# iot-terminal-shield.net
KiCad netlist of a schematic drawn in EAGLE
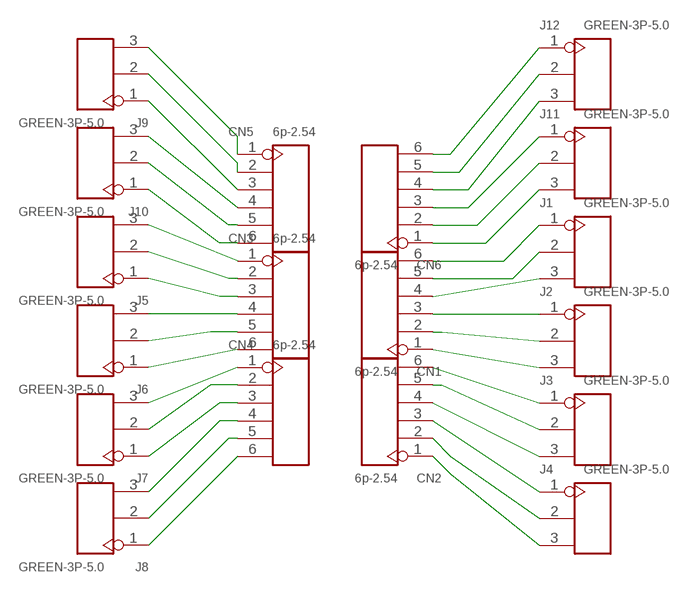
[diagram p0: schematic, sheet 1]

(export (version "E")
  (design (tool "Eeschema 10.0.6"))
  (components
    (comp (ref "CN1")
      (value "6p-2.54")
      (footprint "eagle-import:H6-2.54")
      (fields (field (name "MPN") "F185-1106A1BSYC1"))
      (libsource (lib "eagle-import") (part "DIP-BLACK-FEMALE-HEADER-VERT(6P-2.54)"))
    )
    (comp (ref "CN2")
      (value "6p-2.54")
      (footprint "eagle-import:H6-2.54")
      (fields (field (name "MPN") "F185-1106A1BSYC1"))
      (libsource (lib "eagle-import") (part "DIP-BLACK-FEMALE-HEADER-VERT(6P-2.54)"))
    )
    (comp (ref "CN3")
      (value "6p-2.54")
      (footprint "eagle-import:H6-2.54")
      (fields (field (name "MPN") "F185-1106A1BSYC1"))
      (libsource (lib "eagle-import") (part "DIP-BLACK-FEMALE-HEADER-VERT(6P-2.54)"))
    )
    (comp (ref "CN4")
      (value "6p-2.54")
      (footprint "eagle-import:H6-2.54")
      (fields (field (name "MPN") "F185-1106A1BSYC1"))
      (libsource (lib "eagle-import") (part "DIP-BLACK-FEMALE-HEADER-VERT(6P-2.54)"))
    )
    (comp (ref "CN5")
      (value "6p-2.54")
      (footprint "eagle-import:H6-2.54")
      (fields (field (name "MPN") "F185-1106A1BSYC1"))
      (libsource (lib "eagle-import") (part "DIP-BLACK-FEMALE-HEADER-VERT(6P-2.54)"))
    )
    (comp (ref "CN6")
      (value "6p-2.54")
      (footprint "eagle-import:H6-2.54")
      (fields (field (name "MPN") "F185-1106A1BSYC1"))
      (libsource (lib "eagle-import") (part "DIP-BLACK-FEMALE-HEADER-VERT(6P-2.54)"))
    )
    (comp (ref "J1")
      (value "GREEN-3P-5.0")
      (footprint "eagle-import:H3-5.0-15.5X8.0MM")
      (libsource (lib "eagle-import") (part "SCREW-TERMINAL-GREEN(3P-5.0)"))
    )
    (comp (ref "J2")
      (value "GREEN-3P-5.0")
      (footprint "eagle-import:H3-5.0-15.5X8.0MM")
      (libsource (lib "eagle-import") (part "SCREW-TERMINAL-GREEN(3P-5.0)"))
    )
    (comp (ref "J3")
      (value "GREEN-3P-5.0")
      (footprint "eagle-import:H3-5.0-15.5X8.0MM")
      (libsource (lib "eagle-import") (part "SCREW-TERMINAL-GREEN(3P-5.0)"))
    )
    (comp (ref "J4")
      (value "GREEN-3P-5.0")
      (footprint "eagle-import:H3-5.0-15.5X8.0MM")
      (libsource (lib "eagle-import") (part "SCREW-TERMINAL-GREEN(3P-5.0)"))
    )
    (comp (ref "J5")
      (value "GREEN-3P-5.0")
      (footprint "eagle-import:H3-5.0-15.5X8.0MM")
      (libsource (lib "eagle-import") (part "SCREW-TERMINAL-GREEN(3P-5.0)"))
    )
    (comp (ref "J6")
      (value "GREEN-3P-5.0")
      (footprint "eagle-import:H3-5.0-15.5X8.0MM")
      (libsource (lib "eagle-import") (part "SCREW-TERMINAL-GREEN(3P-5.0)"))
    )
    (comp (ref "J7")
      (value "GREEN-3P-5.0")
      (footprint "eagle-import:H3-5.0-15.5X8.0MM")
      (libsource (lib "eagle-import") (part "SCREW-TERMINAL-GREEN(3P-5.0)"))
    )
    (comp (ref "J8")
      (value "GREEN-3P-5.0")
      (footprint "eagle-import:H3-5.0-15.5X8.0MM")
      (libsource (lib "eagle-import") (part "SCREW-TERMINAL-GREEN(3P-5.0)"))
    )
    (comp (ref "J9")
      (value "GREEN-3P-5.0")
      (footprint "eagle-import:H3-5.0-15.5X8.0MM")
      (libsource (lib "eagle-import") (part "SCREW-TERMINAL-GREEN(3P-5.0)"))
    )
    (comp (ref "J10")
      (value "GREEN-3P-5.0")
      (footprint "eagle-import:H3-5.0-15.5X8.0MM")
      (libsource (lib "eagle-import") (part "SCREW-TERMINAL-GREEN(3P-5.0)"))
    )
    (comp (ref "J11")
      (value "GREEN-3P-5.0")
      (footprint "eagle-import:H3-5.0-15.5X8.0MM")
      (libsource (lib "eagle-import") (part "SCREW-TERMINAL-GREEN(3P-5.0)"))
    )
    (comp (ref "J12")
      (value "GREEN-3P-5.0")
      (footprint "eagle-import:H3-5.0-15.5X8.0MM")
      (libsource (lib "eagle-import") (part "SCREW-TERMINAL-GREEN(3P-5.0)"))
    )
  )
  (nets
    (net (code "1") (name "Net-(J1-P$1)") (class "Default")
      (node (ref "CN1") (pin "6") (pinfunction "6_6") (pintype "bidirectional"))
      (node (ref "J1") (pin "1") (pinfunction "P$1_1") (pintype "bidirectional"))
    )
    (net (code "2") (name "Net-(J1-P$2)") (class "Default")
      (node (ref "CN1") (pin "5") (pinfunction "5_5") (pintype "bidirectional"))
      (node (ref "J1") (pin "2") (pinfunction "P$2_2") (pintype "bidirectional"))
    )
    (net (code "3") (name "Net-(J1-P$3)") (class "Default")
      (node (ref "CN1") (pin "4") (pinfunction "4_4") (pintype "bidirectional"))
      (node (ref "J1") (pin "3") (pinfunction "P$3_3") (pintype "bidirectional"))
    )
    (net (code "4") (name "Net-(J2-P$1)") (class "Default")
      (node (ref "CN1") (pin "3") (pinfunction "3_3") (pintype "bidirectional"))
      (node (ref "J2") (pin "1") (pinfunction "P$1_1") (pintype "bidirectional"))
    )
    (net (code "5") (name "Net-(J2-P$2)") (class "Default")
      (node (ref "CN1") (pin "2") (pinfunction "2_2") (pintype "bidirectional"))
      (node (ref "J2") (pin "2") (pinfunction "P$2_2") (pintype "bidirectional"))
    )
    (net (code "6") (name "Net-(J2-P$3)") (class "Default")
      (node (ref "CN1") (pin "1") (pinfunction "1_1") (pintype "bidirectional"))
      (node (ref "J2") (pin "3") (pinfunction "P$3_3") (pintype "bidirectional"))
    )
    (net (code "7") (name "Net-(J3-P$1)") (class "Default")
      (node (ref "CN2") (pin "6") (pinfunction "6_6") (pintype "bidirectional"))
      (node (ref "J3") (pin "1") (pinfunction "P$1_1") (pintype "bidirectional"))
    )
    (net (code "8") (name "Net-(J3-P$2)") (class "Default")
      (node (ref "CN2") (pin "5") (pinfunction "5_5") (pintype "bidirectional"))
      (node (ref "J3") (pin "2") (pinfunction "P$2_2") (pintype "bidirectional"))
    )
    (net (code "9") (name "Net-(J3-P$3)") (class "Default")
      (node (ref "CN2") (pin "4") (pinfunction "4_4") (pintype "bidirectional"))
      (node (ref "J3") (pin "3") (pinfunction "P$3_3") (pintype "bidirectional"))
    )
    (net (code "10") (name "Net-(J4-P$1)") (class "Default")
      (node (ref "CN2") (pin "3") (pinfunction "3_3") (pintype "bidirectional"))
      (node (ref "J4") (pin "1") (pinfunction "P$1_1") (pintype "bidirectional"))
    )
    (net (code "11") (name "Net-(J4-P$2)") (class "Default")
      (node (ref "CN2") (pin "2") (pinfunction "2_2") (pintype "bidirectional"))
      (node (ref "J4") (pin "2") (pinfunction "P$2_2") (pintype "bidirectional"))
    )
    (net (code "12") (name "Net-(J4-P$3)") (class "Default")
      (node (ref "CN2") (pin "1") (pinfunction "1_1") (pintype "bidirectional"))
      (node (ref "J4") (pin "3") (pinfunction "P$3_3") (pintype "bidirectional"))
    )
    (net (code "13") (name "Net-(J5-P$1)") (class "Default")
      (node (ref "CN3") (pin "3") (pinfunction "3_3") (pintype "bidirectional"))
      (node (ref "J5") (pin "1") (pinfunction "P$1_1") (pintype "bidirectional"))
    )
    (net (code "14") (name "Net-(J5-P$2)") (class "Default")
      (node (ref "CN3") (pin "2") (pinfunction "2_2") (pintype "bidirectional"))
      (node (ref "J5") (pin "2") (pinfunction "P$2_2") (pintype "bidirectional"))
    )
    (net (code "15") (name "Net-(J5-P$3)") (class "Default")
      (node (ref "CN3") (pin "1") (pinfunction "1_1") (pintype "bidirectional"))
      (node (ref "J5") (pin "3") (pinfunction "P$3_3") (pintype "bidirectional"))
    )
    (net (code "16") (name "Net-(J6-P$1)") (class "Default")
      (node (ref "CN3") (pin "6") (pinfunction "6_6") (pintype "bidirectional"))
      (node (ref "J6") (pin "1") (pinfunction "P$1_1") (pintype "bidirectional"))
    )
    (net (code "17") (name "Net-(J6-P$2)") (class "Default")
      (node (ref "CN3") (pin "5") (pinfunction "5_5") (pintype "bidirectional"))
      (node (ref "J6") (pin "2") (pinfunction "P$2_2") (pintype "bidirectional"))
    )
    (net (code "18") (name "Net-(J6-P$3)") (class "Default")
      (node (ref "CN3") (pin "4") (pinfunction "4_4") (pintype "bidirectional"))
      (node (ref "J6") (pin "3") (pinfunction "P$3_3") (pintype "bidirectional"))
    )
    (net (code "19") (name "Net-(J7-P$1)") (class "Default")
      (node (ref "CN4") (pin "3") (pinfunction "3_3") (pintype "bidirectional"))
      (node (ref "J7") (pin "1") (pinfunction "P$1_1") (pintype "bidirectional"))
    )
    (net (code "20") (name "Net-(J7-P$2)") (class "Default")
      (node (ref "CN4") (pin "2") (pinfunction "2_2") (pintype "bidirectional"))
      (node (ref "J7") (pin "2") (pinfunction "P$2_2") (pintype "bidirectional"))
    )
    (net (code "21") (name "Net-(J7-P$3)") (class "Default")
      (node (ref "CN4") (pin "1") (pinfunction "1_1") (pintype "bidirectional"))
      (node (ref "J7") (pin "3") (pinfunction "P$3_3") (pintype "bidirectional"))
    )
    (net (code "22") (name "Net-(J8-P$1)") (class "Default")
      (node (ref "CN4") (pin "6") (pinfunction "6_6") (pintype "bidirectional"))
      (node (ref "J8") (pin "1") (pinfunction "P$1_1") (pintype "bidirectional"))
    )
    (net (code "23") (name "Net-(J8-P$2)") (class "Default")
      (node (ref "CN4") (pin "5") (pinfunction "5_5") (pintype "bidirectional"))
      (node (ref "J8") (pin "2") (pinfunction "P$2_2") (pintype "bidirectional"))
    )
    (net (code "24") (name "Net-(J8-P$3)") (class "Default")
      (node (ref "CN4") (pin "4") (pinfunction "4_4") (pintype "bidirectional"))
      (node (ref "J8") (pin "3") (pinfunction "P$3_3") (pintype "bidirectional"))
    )
    (net (code "25") (name "Net-(J9-P$1)") (class "Default")
      (node (ref "CN5") (pin "3") (pinfunction "3_3") (pintype "bidirectional"))
      (node (ref "J9") (pin "1") (pinfunction "P$1_1") (pintype "bidirectional"))
    )
    (net (code "26") (name "Net-(J9-P$2)") (class "Default")
      (node (ref "CN5") (pin "2") (pinfunction "2_2") (pintype "bidirectional"))
      (node (ref "J9") (pin "2") (pinfunction "P$2_2") (pintype "bidirectional"))
    )
    (net (code "27") (name "Net-(J9-P$3)") (class "Default")
      (node (ref "CN5") (pin "1") (pinfunction "1_1") (pintype "bidirectional"))
      (node (ref "J9") (pin "3") (pinfunction "P$3_3") (pintype "bidirectional"))
    )
    (net (code "28") (name "Net-(J10-P$1)") (class "Default")
      (node (ref "CN5") (pin "6") (pinfunction "6_6") (pintype "bidirectional"))
      (node (ref "J10") (pin "1") (pinfunction "P$1_1") (pintype "bidirectional"))
    )
    (net (code "29") (name "Net-(J10-P$2)") (class "Default")
      (node (ref "CN5") (pin "5") (pinfunction "5_5") (pintype "bidirectional"))
      (node (ref "J10") (pin "2") (pinfunction "P$2_2") (pintype "bidirectional"))
    )
    (net (code "30") (name "Net-(J10-P$3)") (class "Default")
      (node (ref "CN5") (pin "4") (pinfunction "4_4") (pintype "bidirectional"))
      (node (ref "J10") (pin "3") (pinfunction "P$3_3") (pintype "bidirectional"))
    )
    (net (code "31") (name "Net-(J11-P$1)") (class "Default")
      (node (ref "CN6") (pin "3") (pinfunction "3_3") (pintype "bidirectional"))
      (node (ref "J11") (pin "1") (pinfunction "P$1_1") (pintype "bidirectional"))
    )
    (net (code "32") (name "Net-(J11-P$2)") (class "Default")
      (node (ref "CN6") (pin "2") (pinfunction "2_2") (pintype "bidirectional"))
      (node (ref "J11") (pin "2") (pinfunction "P$2_2") (pintype "bidirectional"))
    )
    (net (code "33") (name "Net-(J11-P$3)") (class "Default")
      (node (ref "CN6") (pin "1") (pinfunction "1_1") (pintype "bidirectional"))
      (node (ref "J11") (pin "3") (pinfunction "P$3_3") (pintype "bidirectional"))
    )
    (net (code "34") (name "Net-(J12-P$1)") (class "Default")
      (node (ref "CN6") (pin "6") (pinfunction "6_6") (pintype "bidirectional"))
      (node (ref "J12") (pin "1") (pinfunction "P$1_1") (pintype "bidirectional"))
    )
    (net (code "35") (name "Net-(J12-P$2)") (class "Default")
      (node (ref "CN6") (pin "5") (pinfunction "5_5") (pintype "bidirectional"))
      (node (ref "J12") (pin "2") (pinfunction "P$2_2") (pintype "bidirectional"))
    )
    (net (code "36") (name "Net-(J12-P$3)") (class "Default")
      (node (ref "CN6") (pin "4") (pinfunction "4_4") (pintype "bidirectional"))
      (node (ref "J12") (pin "3") (pinfunction "P$3_3") (pintype "bidirectional"))
    )
  )
)
